# Tester_Charger_Mk2.net
KiCad netlist of a schematic drawn in EAGLE
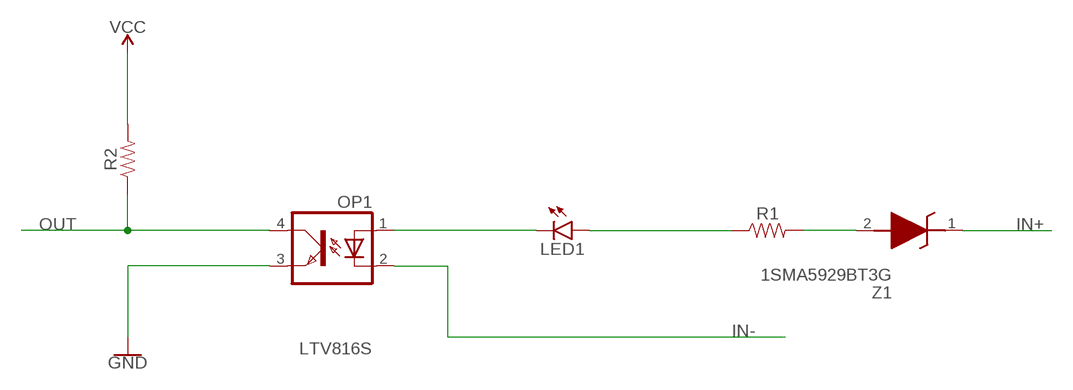
[diagram p0: schematic, sheet 1]

(export (version "E")
  (design (tool "Eeschema 10.0.6"))
  (components
    (comp (ref "LED1")
      (value "LED3MM")
      (footprint "eagle-import:LED3MM")
      (libsource (lib "eagle-import") (part "LED3MM"))
    )
    (comp (ref "OP1")
      (value "LTV816S")
      (footprint "eagle-import:SMD4")
      (libsource (lib "eagle-import") (part "LTV816S"))
    )
    (comp (ref "R1")
      (value "RESISTOR0805")
      (footprint "eagle-import:0805")
      (libsource (lib "eagle-import") (part "RESISTOR0805"))
    )
    (comp (ref "R2")
      (value "RESISTOR0805")
      (footprint "eagle-import:0805")
      (libsource (lib "eagle-import") (part "RESISTOR0805"))
    )
    (comp (ref "Z1")
      (value "1SMA5929BT3G")
      (footprint "eagle-import:DIOM5226X220N")
      (fields (field (name "MOUSER_PART_NUMBER") "863-1SMA5929BT3G"))
      (libsource (lib "eagle-import") (part "1SMA5929BT3G"))
    )
  )
  (nets
    (net (code "1") (name "/IN+") (class "Default")
      (node (ref "Z1") (pin "1") (pinfunction "K_1") (pintype "bidirectional"))
    )
    (net (code "2") (name "/IN-") (class "Default")
      (node (ref "OP1") (pin "2") (pinfunction "C_2") (pintype "passive"))
    )
    (net (code "3") (name "/OUT") (class "Default")
      (node (ref "OP1") (pin "4") (pinfunction "COL_4") (pintype "passive"))
      (node (ref "R2") (pin "1") (pinfunction "1_1") (pintype "passive"))
    )
    (net (code "4") (name "GND") (class "Default")
      (node (ref "OP1") (pin "3") (pinfunction "EMIT_3") (pintype "passive"))
    )
    (net (code "5") (name "Net-(LED1-C)") (class "Default")
      (node (ref "LED1") (pin "K") (pinfunction "C_K") (pintype "passive"))
      (node (ref "OP1") (pin "1") (pinfunction "A_1") (pintype "passive"))
    )
    (net (code "6") (name "Net-(LED1-PadA)") (class "Default")
      (node (ref "LED1") (pin "A") (pinfunction "A_A") (pintype "passive"))
      (node (ref "R1") (pin "1") (pinfunction "1_1") (pintype "passive"))
    )
    (net (code "7") (name "Net-(Z1-A)") (class "Default")
      (node (ref "R1") (pin "2") (pinfunction "2_2") (pintype "passive"))
      (node (ref "Z1") (pin "2") (pinfunction "A_2") (pintype "bidirectional"))
    )
    (net (code "8") (name "VCC") (class "Default")
      (node (ref "R2") (pin "2") (pinfunction "2_2") (pintype "passive"))
    )
  )
)
